# Adafruit_pIRkeyboard.net
KiCad netlist of a schematic drawn in EAGLE
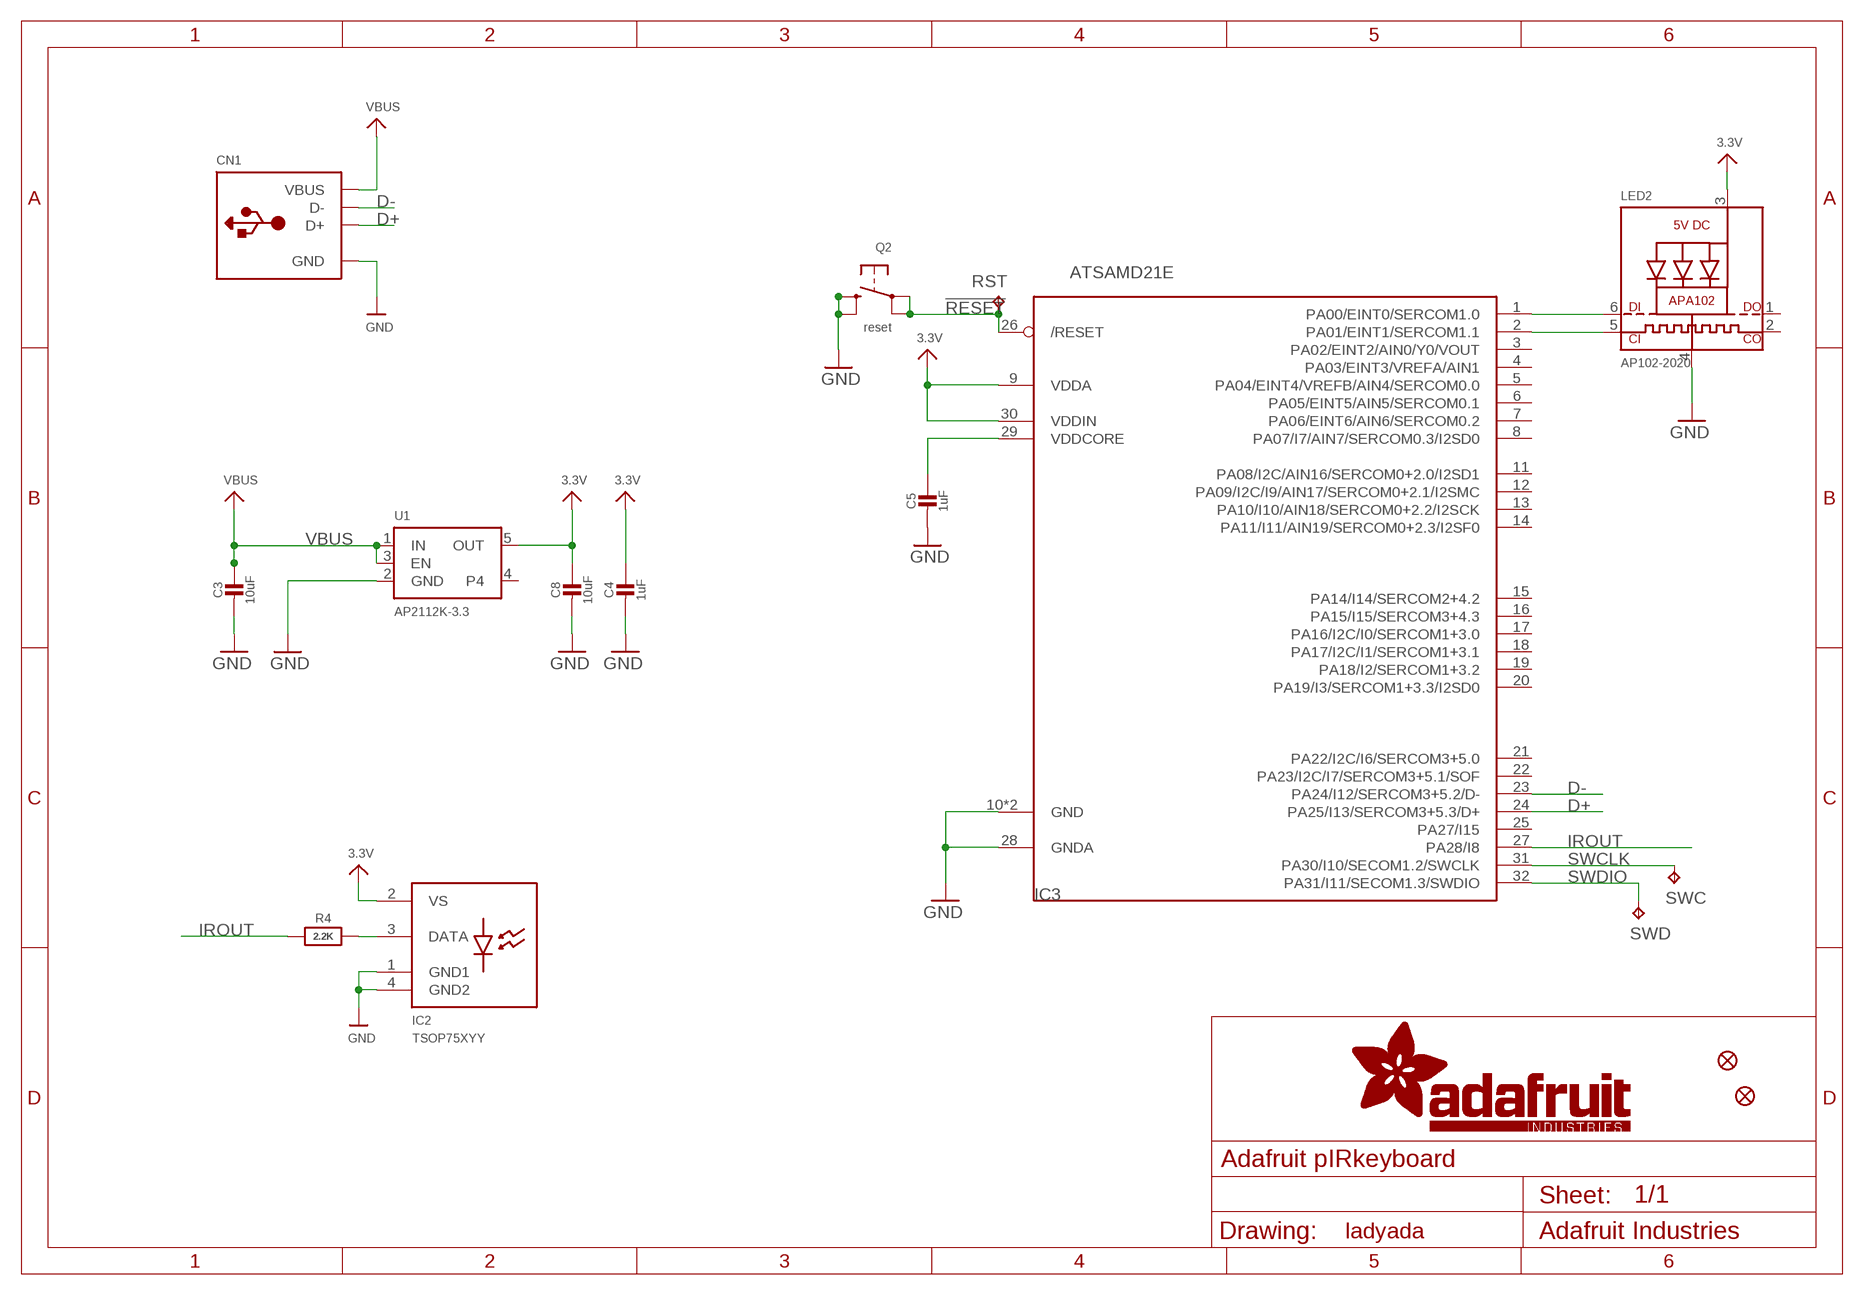
[diagram p0: schematic, sheet 1]

(export (version "E")
  (design (tool "Eeschema 10.0.6"))
  (components
    (comp (ref "C3")
      (value "10uF")
      (footprint "eagle-import:0805-NO")
      (libsource (lib "eagle-import") (part "CAP_CERAMIC0805-NOOUTLINE"))
    )
    (comp (ref "C4")
      (value "1uF")
      (footprint "eagle-import:0603-NO")
      (libsource (lib "eagle-import") (part "CAP_CERAMIC0603_NO"))
    )
    (comp (ref "C5")
      (value "1uF")
      (footprint "eagle-import:0603-NO")
      (libsource (lib "eagle-import") (part "CAP_CERAMIC0603_NO"))
    )
    (comp (ref "C8")
      (value "10uF")
      (footprint "eagle-import:0805-NO")
      (libsource (lib "eagle-import") (part "CAP_CERAMIC0805-NOOUTLINE"))
    )
    (comp (ref "CN1")
      (value "USB_TYPEAPCB")
      (footprint "eagle-import:USBA_PCB")
      (libsource (lib "eagle-import") (part "USB_TYPEAPCB"))
    )
    (comp (ref "FID1")
      (value "FIDUCIAL_1MM")
      (footprint "eagle-import:FIDUCIAL_1MM")
      (libsource (lib "eagle-import") (part "FIDUCIAL_1MM"))
    )
    (comp (ref "FID2")
      (value "FIDUCIAL_1MM")
      (footprint "eagle-import:FIDUCIAL_1MM")
      (libsource (lib "eagle-import") (part "FIDUCIAL_1MM"))
    )
    (comp (ref "IC2")
      (value "TSOP75XYY")
      (footprint "eagle-import:TSOP75XYY")
      (libsource (lib "eagle-import") (part "TSOP75XYY"))
    )
    (comp (ref "IC3")
      (value "ATSAMD21E")
      (footprint "eagle-import:QFN32_5MM")
      (libsource (lib "eagle-import") (part "ATSAMD21E"))
    )
    (comp (ref "LED2")
      (value "AP102-2020")
      (footprint "eagle-import:APA102_2020")
      (libsource (lib "eagle-import") (part "APA1022020"))
    )
    (comp (ref "Q2")
      (value "reset")
      (footprint "eagle-import:BTN_KMR2_4.6X2.8")
      (libsource (lib "eagle-import") (part "SWITCH_TACT_SMT4.6X2.8"))
    )
    (comp (ref "R4")
      (value "2.2K")
      (footprint "eagle-import:0603-NO")
      (libsource (lib "eagle-import") (part "RESISTOR_0603_NOOUT"))
    )
    (comp (ref "RST")
      (value "TPTP16R")
      (footprint "eagle-import:TP16R")
      (libsource (lib "eagle-import") (part "TPTP16R"))
    )
    (comp (ref "SWC")
      (value "TPTP15R")
      (footprint "eagle-import:TP15R")
      (libsource (lib "eagle-import") (part "TPTP15R"))
    )
    (comp (ref "SWD")
      (value "TPTP16R")
      (footprint "eagle-import:TP16R")
      (libsource (lib "eagle-import") (part "TPTP16R"))
    )
    (comp (ref "U1")
      (value "AP2112K-3.3")
      (footprint "eagle-import:SOT23-5")
      (libsource (lib "eagle-import") (part "VREG_SOT23-5"))
    )
  )
  (nets
    (net (code "1") (name "/D+") (class "Default")
      (node (ref "CN1") (pin "USB_PLUS") (pinfunction "D+_USB_PLUS") (pintype "bidirectional"))
      (node (ref "IC3") (pin "24") (pinfunction "PA25/I13/SERCOM3+5.3/D+_24") (pintype "bidirectional"))
    )
    (net (code "2") (name "/D-") (class "Default")
      (node (ref "CN1") (pin "USB_NEG") (pinfunction "D-_USB_NEG") (pintype "bidirectional"))
      (node (ref "IC3") (pin "23") (pinfunction "PA24/I12/SERCOM3+5.2/D-_23") (pintype "bidirectional"))
    )
    (net (code "3") (name "/IROUT") (class "Default")
      (node (ref "IC3") (pin "27") (pinfunction "PA28/I8_27") (pintype "bidirectional"))
      (node (ref "R4") (pin "1") (pinfunction "1_1") (pintype "passive"))
    )
    (net (code "4") (name "/SWCLK") (class "Default")
      (node (ref "IC3") (pin "31") (pinfunction "PA30/I10/SECOM1.2/SWCLK_31") (pintype "bidirectional"))
      (node (ref "SWC") (pin "TP") (pinfunction "TP_TP") (pintype "input"))
    )
    (net (code "5") (name "/SWDIO") (class "Default")
      (node (ref "IC3") (pin "32") (pinfunction "PA31/I11/SECOM1.3/SWDIO_32") (pintype "bidirectional"))
      (node (ref "SWD") (pin "TP") (pinfunction "TP_TP") (pintype "input"))
    )
    (net (code "6") (name "/~{RESET}") (class "Default")
      (node (ref "IC3") (pin "26") (pinfunction "/RESET_26") (pintype "bidirectional"))
      (node (ref "Q2") (pin "A") (pinfunction "P_A") (pintype "passive"))
      (node (ref "Q2") (pin "A'") (pinfunction "P1_A'") (pintype "passive"))
      (node (ref "RST") (pin "TP") (pinfunction "TP_TP") (pintype "input"))
    )
    (net (code "7") (name "3.3V") (class "Default")
      (node (ref "C4") (pin "1") (pinfunction "1_1") (pintype "passive"))
      (node (ref "C8") (pin "1") (pinfunction "1_1") (pintype "passive"))
      (node (ref "IC2") (pin "2") (pinfunction "VS_2") (pintype "passive"))
      (node (ref "IC3") (pin "30") (pinfunction "VDDIN_30") (pintype "power_in"))
      (node (ref "IC3") (pin "9") (pinfunction "VDDA_9") (pintype "power_in"))
      (node (ref "LED2") (pin "3") (pinfunction "VDD_3") (pintype "power_in"))
      (node (ref "U1") (pin "5") (pinfunction "OUT_5") (pintype "power_in"))
    )
    (net (code "8") (name "GND") (class "Default")
      (node (ref "C3") (pin "2") (pinfunction "2_2") (pintype "passive"))
      (node (ref "C4") (pin "2") (pinfunction "2_2") (pintype "passive"))
      (node (ref "C5") (pin "2") (pinfunction "2_2") (pintype "passive"))
      (node (ref "C8") (pin "2") (pinfunction "2_2") (pintype "passive"))
      (node (ref "CN1") (pin "GND") (pinfunction "GND_GND") (pintype "power_in"))
      (node (ref "IC2") (pin "1") (pinfunction "GND1_1") (pintype "passive"))
      (node (ref "IC2") (pin "4") (pinfunction "GND2_4") (pintype "passive"))
      (node (ref "IC3") (pin "10") (pinfunction "GND_10") (pintype "power_in"))
      (node (ref "IC3") (pin "28") (pinfunction "GNDA_28") (pintype "power_in"))
      (node (ref "IC3") (pin "33") (pinfunction "GND_33") (pintype "power_in"))
      (node (ref "LED2") (pin "4") (pinfunction "GND_4") (pintype "power_in"))
      (node (ref "Q2") (pin "B") (pinfunction "S_B") (pintype "passive"))
      (node (ref "Q2") (pin "B'") (pinfunction "S1_B'") (pintype "passive"))
      (node (ref "U1") (pin "2") (pinfunction "GND_2") (pintype "power_in"))
    )
    (net (code "9") (name "Net-(IC2-DATA)") (class "Default")
      (node (ref "IC2") (pin "3") (pinfunction "DATA_3") (pintype "output"))
      (node (ref "R4") (pin "2") (pinfunction "2_2") (pintype "passive"))
    )
    (net (code "10") (name "Net-(IC3-PA00{slash}EINT0{slash}SERCOM1.0)") (class "Default")
      (node (ref "IC3") (pin "1") (pinfunction "PA00/EINT0/SERCOM1.0_1") (pintype "bidirectional"))
      (node (ref "LED2") (pin "6") (pinfunction "DI_6") (pintype "input"))
    )
    (net (code "11") (name "Net-(IC3-PA01{slash}EINT1{slash}SERCOM1.1)") (class "Default")
      (node (ref "IC3") (pin "2") (pinfunction "PA01/EINT1/SERCOM1.1_2") (pintype "bidirectional"))
      (node (ref "LED2") (pin "5") (pinfunction "CKI_5") (pintype "input"))
    )
    (net (code "12") (name "Net-(IC3-VDDCORE)") (class "Default")
      (node (ref "C5") (pin "1") (pinfunction "1_1") (pintype "passive"))
      (node (ref "IC3") (pin "29") (pinfunction "VDDCORE_29") (pintype "power_in"))
    )
    (net (code "13") (name "VBUS") (class "Default")
      (node (ref "C3") (pin "1") (pinfunction "1_1") (pintype "passive"))
      (node (ref "CN1") (pin "VCC") (pinfunction "VBUS_VCC") (pintype "power_in"))
      (node (ref "U1") (pin "1") (pinfunction "IN_1") (pintype "power_in"))
      (node (ref "U1") (pin "3") (pinfunction "EN_3") (pintype "input"))
    )
    (net (code "14") (name "unconnected-(IC3-PA02{slash}EINT2{slash}AIN0{slash}Y0{slash}VOUT-Pad3)") (class "Default")
      (node (ref "IC3") (pin "3") (pinfunction "PA02/EINT2/AIN0/Y0/VOUT_3") (pintype "bidirectional"))
    )
    (net (code "15") (name "unconnected-(IC3-PA03{slash}EINT3{slash}VREFA{slash}AIN1-Pad4)") (class "Default")
      (node (ref "IC3") (pin "4") (pinfunction "PA03/EINT3/VREFA/AIN1_4") (pintype "bidirectional"))
    )
    (net (code "16") (name "unconnected-(IC3-PA04{slash}EINT4{slash}VREFB{slash}AIN4{slash}SERCOM0.0-Pad5)") (class "Default")
      (node (ref "IC3") (pin "5") (pinfunction "PA04/EINT4/VREFB/AIN4/SERCOM0.0_5") (pintype "bidirectional"))
    )
    (net (code "17") (name "unconnected-(IC3-PA05{slash}EINT5{slash}AIN5{slash}SERCOM0.1-Pad6)") (class "Default")
      (node (ref "IC3") (pin "6") (pinfunction "PA05/EINT5/AIN5/SERCOM0.1_6") (pintype "bidirectional"))
    )
    (net (code "18") (name "unconnected-(IC3-PA06{slash}EINT6{slash}AIN6{slash}SERCOM0.2-Pad7)") (class "Default")
      (node (ref "IC3") (pin "7") (pinfunction "PA06/EINT6/AIN6/SERCOM0.2_7") (pintype "bidirectional"))
    )
    (net (code "19") (name "unconnected-(IC3-PA07{slash}I7{slash}AIN7{slash}SERCOM0.3{slash}I2SD0-Pad8)") (class "Default")
      (node (ref "IC3") (pin "8") (pinfunction "PA07/I7/AIN7/SERCOM0.3/I2SD0_8") (pintype "bidirectional"))
    )
    (net (code "20") (name "unconnected-(IC3-PA08{slash}I2C{slash}AIN16{slash}SERCOM0+2.0{slash}I2SD1-Pad11)") (class "Default")
      (node (ref "IC3") (pin "11") (pinfunction "PA08/I2C/AIN16/SERCOM0+2.0/I2SD1_11") (pintype "bidirectional"))
    )
    (net (code "21") (name "unconnected-(IC3-PA09{slash}I2C{slash}I9{slash}AIN17{slash}SERCOM0+2.1{slash}I2SMC-Pad12)") (class "Default")
      (node (ref "IC3") (pin "12") (pinfunction "PA09/I2C/I9/AIN17/SERCOM0+2.1/I2SMC_12") (pintype "bidirectional"))
    )
    (net (code "22") (name "unconnected-(IC3-PA10{slash}I10{slash}AIN18{slash}SERCOM0+2.2{slash}I2SCK-Pad13)") (class "Default")
      (node (ref "IC3") (pin "13") (pinfunction "PA10/I10/AIN18/SERCOM0+2.2/I2SCK_13") (pintype "bidirectional"))
    )
    (net (code "23") (name "unconnected-(IC3-PA11{slash}I11{slash}AIN19{slash}SERCOM0+2.3{slash}I2SF0-Pad14)") (class "Default")
      (node (ref "IC3") (pin "14") (pinfunction "PA11/I11/AIN19/SERCOM0+2.3/I2SF0_14") (pintype "bidirectional"))
    )
    (net (code "24") (name "unconnected-(IC3-PA14{slash}I14{slash}SERCOM2+4.2-Pad15)") (class "Default")
      (node (ref "IC3") (pin "15") (pinfunction "PA14/I14/SERCOM2+4.2_15") (pintype "bidirectional"))
    )
    (net (code "25") (name "unconnected-(IC3-PA15{slash}I15{slash}SERCOM3+4.3-Pad16)") (class "Default")
      (node (ref "IC3") (pin "16") (pinfunction "PA15/I15/SERCOM3+4.3_16") (pintype "bidirectional"))
    )
    (net (code "26") (name "unconnected-(IC3-PA16{slash}I2C{slash}I0{slash}SERCOM1+3.0-Pad17)") (class "Default")
      (node (ref "IC3") (pin "17") (pinfunction "PA16/I2C/I0/SERCOM1+3.0_17") (pintype "bidirectional"))
    )
    (net (code "27") (name "unconnected-(IC3-PA17{slash}I2C{slash}I1{slash}SERCOM1+3.1-Pad18)") (class "Default")
      (node (ref "IC3") (pin "18") (pinfunction "PA17/I2C/I1/SERCOM1+3.1_18") (pintype "bidirectional"))
    )
    (net (code "28") (name "unconnected-(IC3-PA18{slash}I2{slash}SERCOM1+3.2-Pad19)") (class "Default")
      (node (ref "IC3") (pin "19") (pinfunction "PA18/I2/SERCOM1+3.2_19") (pintype "bidirectional"))
    )
    (net (code "29") (name "unconnected-(IC3-PA19{slash}I3{slash}SERCOM1+3.3{slash}I2SD0-Pad20)") (class "Default")
      (node (ref "IC3") (pin "20") (pinfunction "PA19/I3/SERCOM1+3.3/I2SD0_20") (pintype "bidirectional"))
    )
    (net (code "30") (name "unconnected-(IC3-PA22{slash}I2C{slash}I6{slash}SERCOM3+5.0-Pad21)") (class "Default")
      (node (ref "IC3") (pin "21") (pinfunction "PA22/I2C/I6/SERCOM3+5.0_21") (pintype "bidirectional"))
    )
    (net (code "31") (name "unconnected-(IC3-PA23{slash}I2C{slash}I7{slash}SERCOM3+5.1{slash}SOF-Pad22)") (class "Default")
      (node (ref "IC3") (pin "22") (pinfunction "PA23/I2C/I7/SERCOM3+5.1/SOF_22") (pintype "bidirectional"))
    )
    (net (code "32") (name "unconnected-(IC3-PA27{slash}I15-Pad25)") (class "Default")
      (node (ref "IC3") (pin "25") (pinfunction "PA27/I15_25") (pintype "bidirectional"))
    )
    (net (code "33") (name "unconnected-(LED2-CKO-Pad2)") (class "Default")
      (node (ref "LED2") (pin "2") (pinfunction "CKO_2") (pintype "output"))
    )
    (net (code "34") (name "unconnected-(LED2-DO-Pad1)") (class "Default")
      (node (ref "LED2") (pin "1") (pinfunction "DO_1") (pintype "output"))
    )
    (net (code "35") (name "unconnected-(U1-P4-Pad4)") (class "Default")
      (node (ref "U1") (pin "4") (pinfunction "P4_4") (pintype "bidirectional"))
    )
  )
)
